# sensor_board.net
KiCad netlist of a schematic drawn in EAGLE
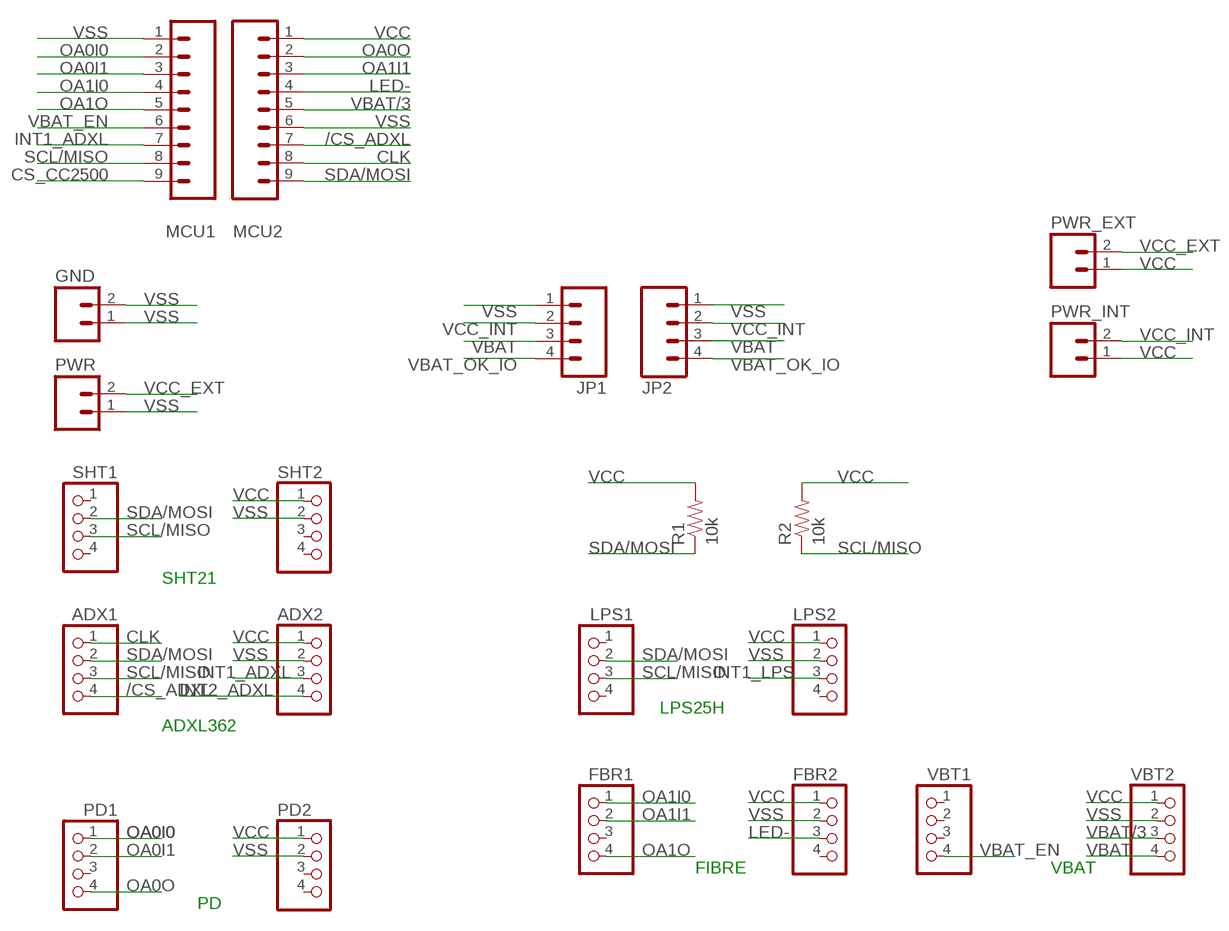
[diagram p0: schematic, sheet 1]

(export (version "E")
  (design (tool "Eeschema 10.0.6"))
  (components
    (comp (ref "ADX1")
      (value "PINHD-1X4")
      (footprint "eagle-import:1X04")
      (libsource (lib "eagle-import") (part "PINHD-1X4"))
    )
    (comp (ref "ADX2")
      (value "PINHD-1X4")
      (footprint "eagle-import:1X04")
      (libsource (lib "eagle-import") (part "PINHD-1X4"))
    )
    (comp (ref "FBR1")
      (value "PINHD-1X4")
      (footprint "eagle-import:1X04")
      (libsource (lib "eagle-import") (part "PINHD-1X4"))
    )
    (comp (ref "FBR2")
      (value "PINHD-1X4")
      (footprint "eagle-import:1X04")
      (libsource (lib "eagle-import") (part "PINHD-1X4"))
    )
    (comp (ref "GND")
      (value "M02PTH")
      (footprint "eagle-import:1X02")
      (libsource (lib "eagle-import") (part "M02PTH"))
    )
    (comp (ref "JP1")
      (value "M04PTH")
      (footprint "eagle-import:1X04")
      (libsource (lib "eagle-import") (part "M04PTH"))
    )
    (comp (ref "JP2")
      (value "M04PTH")
      (footprint "eagle-import:1X04")
      (libsource (lib "eagle-import") (part "M04PTH"))
    )
    (comp (ref "LPS1")
      (value "PINHD-1X4")
      (footprint "eagle-import:1X04")
      (libsource (lib "eagle-import") (part "PINHD-1X4"))
    )
    (comp (ref "LPS2")
      (value "PINHD-1X4")
      (footprint "eagle-import:1X04")
      (libsource (lib "eagle-import") (part "PINHD-1X4"))
    )
    (comp (ref "MCU1")
      (value "M09")
      (footprint "eagle-import:1X09")
      (libsource (lib "eagle-import") (part "M09"))
    )
    (comp (ref "MCU2")
      (value "M09")
      (footprint "eagle-import:1X09")
      (libsource (lib "eagle-import") (part "M09"))
    )
    (comp (ref "PD1")
      (value "PINHD-1X4")
      (footprint "eagle-import:1X04")
      (libsource (lib "eagle-import") (part "PINHD-1X4"))
    )
    (comp (ref "PD2")
      (value "PINHD-1X4")
      (footprint "eagle-import:1X04")
      (libsource (lib "eagle-import") (part "PINHD-1X4"))
    )
    (comp (ref "PWR")
      (value "M02PTH")
      (footprint "eagle-import:1X02")
      (libsource (lib "eagle-import") (part "M02PTH"))
    )
    (comp (ref "PWR_EXT")
      (value "M02PTH")
      (footprint "eagle-import:1X02")
      (libsource (lib "eagle-import") (part "M02PTH"))
    )
    (comp (ref "PWR_INT")
      (value "M02PTH")
      (footprint "eagle-import:1X02")
      (libsource (lib "eagle-import") (part "M02PTH"))
    )
    (comp (ref "R1")
      (value "10k")
      (footprint "eagle-import:AXIAL-0.3")
      (libsource (lib "eagle-import") (part "10KOHM-1/4W5%(PTH)"))
    )
    (comp (ref "R2")
      (value "10k")
      (footprint "eagle-import:AXIAL-0.3")
      (libsource (lib "eagle-import") (part "10KOHM-1/4W5%(PTH)"))
    )
    (comp (ref "SHT1")
      (value "PINHD-1X4")
      (footprint "eagle-import:1X04")
      (libsource (lib "eagle-import") (part "PINHD-1X4"))
    )
    (comp (ref "SHT2")
      (value "PINHD-1X4")
      (footprint "eagle-import:1X04")
      (libsource (lib "eagle-import") (part "PINHD-1X4"))
    )
    (comp (ref "VBT1")
      (value "PINHD-1X4")
      (footprint "eagle-import:1X04")
      (libsource (lib "eagle-import") (part "PINHD-1X4"))
    )
    (comp (ref "VBT2")
      (value "PINHD-1X4")
      (footprint "eagle-import:1X04")
      (libsource (lib "eagle-import") (part "PINHD-1X4"))
    )
  )
  (nets
    (net (code "1") (name "/CLK") (class "Default")
      (node (ref "ADX1") (pin "1") (pinfunction "1_1") (pintype "passive"))
      (node (ref "MCU2") (pin "8") (pinfunction "8_8") (pintype "passive"))
    )
    (net (code "2") (name "/CS_CC2500") (class "Default")
      (node (ref "MCU1") (pin "9") (pinfunction "9_9") (pintype "passive"))
    )
    (net (code "3") (name "/INT1_ADXL") (class "Default")
      (node (ref "ADX2") (pin "3") (pinfunction "3_3") (pintype "passive"))
      (node (ref "MCU1") (pin "7") (pinfunction "7_7") (pintype "passive"))
    )
    (net (code "4") (name "/INT1_LPS") (class "Default")
      (node (ref "LPS2") (pin "3") (pinfunction "3_3") (pintype "passive"))
    )
    (net (code "5") (name "/INT2_ADXL") (class "Default")
      (node (ref "ADX2") (pin "4") (pinfunction "4_4") (pintype "passive"))
    )
    (net (code "6") (name "/LED-") (class "Default")
      (node (ref "FBR2") (pin "3") (pinfunction "3_3") (pintype "passive"))
      (node (ref "MCU2") (pin "4") (pinfunction "4_4") (pintype "passive"))
    )
    (net (code "7") (name "/OA0I0") (class "Default")
      (node (ref "MCU1") (pin "2") (pinfunction "2_2") (pintype "passive"))
      (node (ref "PD1") (pin "1") (pinfunction "1_1") (pintype "passive"))
    )
    (net (code "8") (name "/OA0I1") (class "Default")
      (node (ref "MCU1") (pin "3") (pinfunction "3_3") (pintype "passive"))
      (node (ref "PD1") (pin "2") (pinfunction "2_2") (pintype "passive"))
    )
    (net (code "9") (name "/OA0O") (class "Default")
      (node (ref "MCU2") (pin "2") (pinfunction "2_2") (pintype "passive"))
      (node (ref "PD1") (pin "4") (pinfunction "4_4") (pintype "passive"))
    )
    (net (code "10") (name "/OA1I0") (class "Default")
      (node (ref "FBR1") (pin "1") (pinfunction "1_1") (pintype "passive"))
      (node (ref "MCU1") (pin "4") (pinfunction "4_4") (pintype "passive"))
    )
    (net (code "11") (name "/OA1I1") (class "Default")
      (node (ref "FBR1") (pin "2") (pinfunction "2_2") (pintype "passive"))
      (node (ref "MCU2") (pin "3") (pinfunction "3_3") (pintype "passive"))
    )
    (net (code "12") (name "/OA1O") (class "Default")
      (node (ref "FBR1") (pin "4") (pinfunction "4_4") (pintype "passive"))
      (node (ref "MCU1") (pin "5") (pinfunction "5_5") (pintype "passive"))
    )
    (net (code "13") (name "/SCL{slash}MISO") (class "Default")
      (node (ref "ADX1") (pin "3") (pinfunction "3_3") (pintype "passive"))
      (node (ref "LPS1") (pin "3") (pinfunction "3_3") (pintype "passive"))
      (node (ref "MCU1") (pin "8") (pinfunction "8_8") (pintype "passive"))
      (node (ref "R2") (pin "P$1") (pinfunction "1_P$1") (pintype "passive"))
      (node (ref "SHT1") (pin "3") (pinfunction "3_3") (pintype "passive"))
    )
    (net (code "14") (name "/SDA{slash}MOSI") (class "Default")
      (node (ref "ADX1") (pin "2") (pinfunction "2_2") (pintype "passive"))
      (node (ref "LPS1") (pin "2") (pinfunction "2_2") (pintype "passive"))
      (node (ref "MCU2") (pin "9") (pinfunction "9_9") (pintype "passive"))
      (node (ref "R1") (pin "P$1") (pinfunction "1_P$1") (pintype "passive"))
      (node (ref "SHT1") (pin "2") (pinfunction "2_2") (pintype "passive"))
    )
    (net (code "15") (name "/VBAT") (class "Default")
      (node (ref "JP1") (pin "3") (pinfunction "3_3") (pintype "passive"))
      (node (ref "JP2") (pin "3") (pinfunction "3_3") (pintype "passive"))
      (node (ref "VBT2") (pin "4") (pinfunction "4_4") (pintype "passive"))
    )
    (net (code "16") (name "/VBAT_EN") (class "Default")
      (node (ref "MCU1") (pin "6") (pinfunction "6_6") (pintype "passive"))
      (node (ref "VBT1") (pin "4") (pinfunction "4_4") (pintype "passive"))
    )
    (net (code "17") (name "/VBAT_OK_IO") (class "Default")
      (node (ref "JP1") (pin "4") (pinfunction "4_4") (pintype "passive"))
      (node (ref "JP2") (pin "4") (pinfunction "4_4") (pintype "passive"))
    )
    (net (code "18") (name "/VBAT{slash}3") (class "Default")
      (node (ref "MCU2") (pin "5") (pinfunction "5_5") (pintype "passive"))
      (node (ref "VBT2") (pin "3") (pinfunction "3_3") (pintype "passive"))
    )
    (net (code "19") (name "/VCC") (class "Default")
      (node (ref "ADX2") (pin "1") (pinfunction "1_1") (pintype "passive"))
      (node (ref "FBR2") (pin "1") (pinfunction "1_1") (pintype "passive"))
      (node (ref "LPS2") (pin "1") (pinfunction "1_1") (pintype "passive"))
      (node (ref "MCU2") (pin "1") (pinfunction "1_1") (pintype "passive"))
      (node (ref "PD2") (pin "1") (pinfunction "1_1") (pintype "passive"))
      (node (ref "PWR_EXT") (pin "1") (pinfunction "1_1") (pintype "passive"))
      (node (ref "PWR_INT") (pin "1") (pinfunction "1_1") (pintype "passive"))
      (node (ref "R1") (pin "P$2") (pinfunction "2_P$2") (pintype "passive"))
      (node (ref "R2") (pin "P$2") (pinfunction "2_P$2") (pintype "passive"))
      (node (ref "SHT2") (pin "1") (pinfunction "1_1") (pintype "passive"))
      (node (ref "VBT2") (pin "1") (pinfunction "1_1") (pintype "passive"))
    )
    (net (code "20") (name "/VCC_EXT") (class "Default")
      (node (ref "PWR") (pin "2") (pinfunction "2_2") (pintype "passive"))
      (node (ref "PWR_EXT") (pin "2") (pinfunction "2_2") (pintype "passive"))
    )
    (net (code "21") (name "/VCC_INT") (class "Default")
      (node (ref "JP1") (pin "2") (pinfunction "2_2") (pintype "passive"))
      (node (ref "JP2") (pin "2") (pinfunction "2_2") (pintype "passive"))
      (node (ref "PWR_INT") (pin "2") (pinfunction "2_2") (pintype "passive"))
    )
    (net (code "22") (name "/VSS") (class "Default")
      (node (ref "ADX2") (pin "2") (pinfunction "2_2") (pintype "passive"))
      (node (ref "FBR2") (pin "2") (pinfunction "2_2") (pintype "passive"))
      (node (ref "GND") (pin "1") (pinfunction "1_1") (pintype "passive"))
      (node (ref "GND") (pin "2") (pinfunction "2_2") (pintype "passive"))
      (node (ref "JP1") (pin "1") (pinfunction "1_1") (pintype "passive"))
      (node (ref "JP2") (pin "1") (pinfunction "1_1") (pintype "passive"))
      (node (ref "LPS2") (pin "2") (pinfunction "2_2") (pintype "passive"))
      (node (ref "MCU1") (pin "1") (pinfunction "1_1") (pintype "passive"))
      (node (ref "MCU2") (pin "6") (pinfunction "6_6") (pintype "passive"))
      (node (ref "PD2") (pin "2") (pinfunction "2_2") (pintype "passive"))
      (node (ref "PWR") (pin "1") (pinfunction "1_1") (pintype "passive"))
      (node (ref "SHT2") (pin "2") (pinfunction "2_2") (pintype "passive"))
      (node (ref "VBT2") (pin "2") (pinfunction "2_2") (pintype "passive"))
    )
    (net (code "23") (name "/{slash}CS_ADXL") (class "Default")
      (node (ref "ADX1") (pin "4") (pinfunction "4_4") (pintype "passive"))
      (node (ref "MCU2") (pin "7") (pinfunction "7_7") (pintype "passive"))
    )
    (net (code "24") (name "unconnected-(FBR1-Pad3)") (class "Default")
      (node (ref "FBR1") (pin "3") (pinfunction "3_3") (pintype "passive"))
    )
    (net (code "25") (name "unconnected-(FBR2-Pad4)") (class "Default")
      (node (ref "FBR2") (pin "4") (pinfunction "4_4") (pintype "passive"))
    )
    (net (code "26") (name "unconnected-(LPS1-Pad1)") (class "Default")
      (node (ref "LPS1") (pin "1") (pinfunction "1_1") (pintype "passive"))
    )
    (net (code "27") (name "unconnected-(LPS1-Pad4)") (class "Default")
      (node (ref "LPS1") (pin "4") (pinfunction "4_4") (pintype "passive"))
    )
    (net (code "28") (name "unconnected-(LPS2-Pad4)") (class "Default")
      (node (ref "LPS2") (pin "4") (pinfunction "4_4") (pintype "passive"))
    )
    (net (code "29") (name "unconnected-(PD1-Pad3)") (class "Default")
      (node (ref "PD1") (pin "3") (pinfunction "3_3") (pintype "passive"))
    )
    (net (code "30") (name "unconnected-(PD2-Pad3)") (class "Default")
      (node (ref "PD2") (pin "3") (pinfunction "3_3") (pintype "passive"))
    )
    (net (code "31") (name "unconnected-(PD2-Pad4)") (class "Default")
      (node (ref "PD2") (pin "4") (pinfunction "4_4") (pintype "passive"))
    )
    (net (code "32") (name "unconnected-(SHT1-Pad1)") (class "Default")
      (node (ref "SHT1") (pin "1") (pinfunction "1_1") (pintype "passive"))
    )
    (net (code "33") (name "unconnected-(SHT1-Pad4)") (class "Default")
      (node (ref "SHT1") (pin "4") (pinfunction "4_4") (pintype "passive"))
    )
    (net (code "34") (name "unconnected-(SHT2-Pad3)") (class "Default")
      (node (ref "SHT2") (pin "3") (pinfunction "3_3") (pintype "passive"))
    )
    (net (code "35") (name "unconnected-(SHT2-Pad4)") (class "Default")
      (node (ref "SHT2") (pin "4") (pinfunction "4_4") (pintype "passive"))
    )
    (net (code "36") (name "unconnected-(VBT1-Pad1)") (class "Default")
      (node (ref "VBT1") (pin "1") (pinfunction "1_1") (pintype "passive"))
    )
    (net (code "37") (name "unconnected-(VBT1-Pad2)") (class "Default")
      (node (ref "VBT1") (pin "2") (pinfunction "2_2") (pintype "passive"))
    )
    (net (code "38") (name "unconnected-(VBT1-Pad3)") (class "Default")
      (node (ref "VBT1") (pin "3") (pinfunction "3_3") (pintype "passive"))
    )
  )
)
